# ic-mhm-encoder-simple.net
KiCad netlist of a schematic drawn in EAGLE
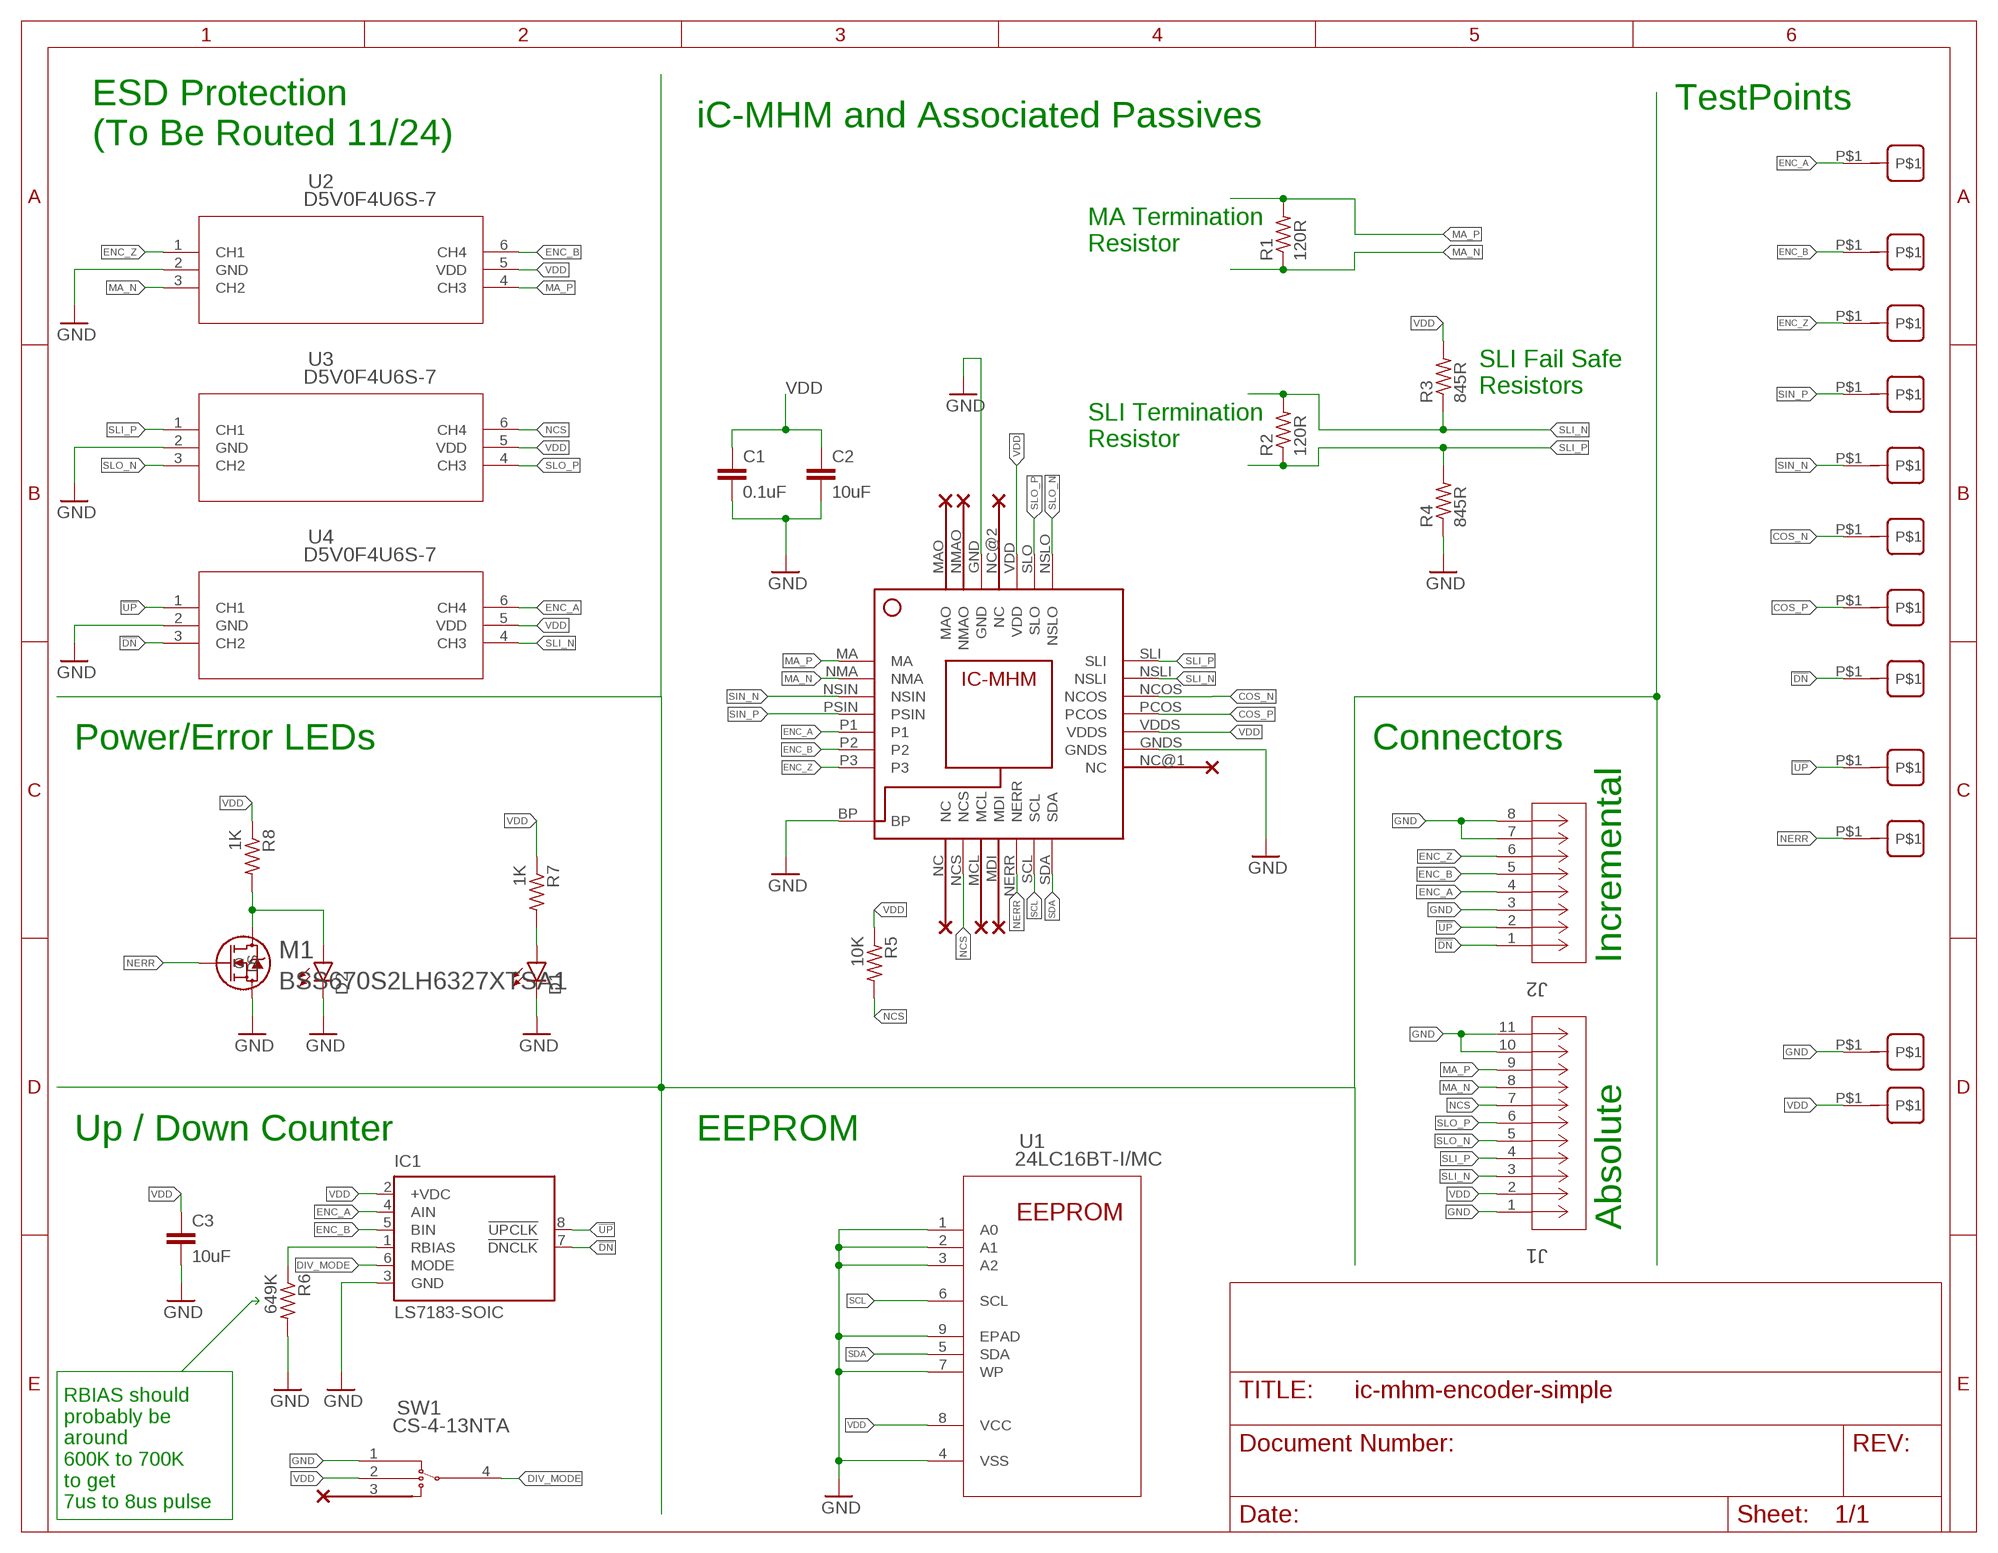
[diagram p0: schematic, sheet 1]

(export (version "E")
  (design (tool "Eeschema 10.0.6"))
  (components
    (comp (ref "C1")
      (value "0.1uF")
      (footprint "eagle-import:C0603")
      (libsource (lib "eagle-import") (part "C-EUC0603"))
    )
    (comp (ref "C2")
      (value "10uF")
      (footprint "eagle-import:C0805")
      (libsource (lib "eagle-import") (part "C-EUC0805"))
    )
    (comp (ref "C3")
      (value "10uF")
      (footprint "eagle-import:C0805")
      (libsource (lib "eagle-import") (part "C-EUC0805"))
    )
    (comp (ref "D1")
      (value "LEDSML0603")
      (footprint "eagle-import:SML0603")
      (libsource (lib "eagle-import") (part "LEDSML0603"))
    )
    (comp (ref "D2")
      (value "LEDSML0603")
      (footprint "eagle-import:SML0603")
      (libsource (lib "eagle-import") (part "LEDSML0603"))
    )
    (comp (ref "IC1")
      (value "LS7183-SOIC")
      (footprint "eagle-import:SOIC08")
      (fields
        (field (name "DIGI-KEY_PART_NUMBER") "2808-LS7183N-S-ND")
        (field (name "MF") "LSI")
        (field (name "MP") "LS7183")
      )
      (libsource (lib "eagle-import") (part "LS7183-SOIC"))
    )
    (comp (ref "J1")
      (value "2023960907")
      (footprint "eagle-import:CON_2023960907")
      (fields (field (name "COPYRIGHT") "Copyright (C) 2021 Ultra Librarian. All rights reserved."))
      (libsource (lib "eagle-import") (part "2023960907"))
    )
    (comp (ref "J2")
      (value "2023960607")
      (footprint "eagle-import:CON_2023960607")
      (fields (field (name "COPYRIGHT") "Copyright (C) 2021 Ultra Librarian. All rights reserved."))
      (libsource (lib "eagle-import") (part "2023960607"))
    )
    (comp (ref "M1")
      (value "BSS670S2LH6327XTSA1")
      (footprint "eagle-import:PG-SOT23-3-5_INF")
      (fields (field (name "COPYRIGHT") "Copyright (C) 2021 Ultra Librarian. All rights reserved."))
      (libsource (lib "eagle-import") (part "BSS670S2LH6327XTSA1"))
    )
    (comp (ref "R1")
      (value "120R")
      (footprint "eagle-import:R0603")
      (libsource (lib "eagle-import") (part "R-US_R0603"))
    )
    (comp (ref "R2")
      (value "120R")
      (footprint "eagle-import:R0603")
      (libsource (lib "eagle-import") (part "R-US_R0603"))
    )
    (comp (ref "R3")
      (value "845R")
      (footprint "eagle-import:R0603")
      (libsource (lib "eagle-import") (part "R-US_R0603"))
    )
    (comp (ref "R4")
      (value "845R")
      (footprint "eagle-import:R0603")
      (libsource (lib "eagle-import") (part "R-US_R0603"))
    )
    (comp (ref "R5")
      (value "10K")
      (footprint "eagle-import:R0603")
      (libsource (lib "eagle-import") (part "R-US_R0603"))
    )
    (comp (ref "R6")
      (value "649K")
      (footprint "eagle-import:R0603")
      (libsource (lib "eagle-import") (part "R-US_R0603"))
    )
    (comp (ref "R7")
      (value "1K")
      (footprint "eagle-import:R0603")
      (libsource (lib "eagle-import") (part "R-US_R0603"))
    )
    (comp (ref "R8")
      (value "1K")
      (footprint "eagle-import:R0603")
      (libsource (lib "eagle-import") (part "R-US_R0603"))
    )
    (comp (ref "SW1")
      (value "CS-4-13NTA")
      (footprint "eagle-import:CS-4-13NA_NDC")
      (fields (field (name "COPYRIGHT") "Copyright (C) 2021 Ultra Librarian. All rights reserved."))
      (libsource (lib "eagle-import") (part "CS-4-13NTA"))
    )
    (comp (ref "U$1")
      (value "IC-MHM")
      (footprint "eagle-import:IC-MHM")
      (libsource (lib "eagle-import") (part "IC-MHM"))
    )
    (comp (ref "U$2")
      (value "TESTPOINT_S1751-46")
      (footprint "eagle-import:TESTPOINT_S1751-46")
      (libsource (lib "eagle-import") (part "TESTPOINT_S1751-46"))
    )
    (comp (ref "U$3")
      (value "TESTPOINT_S1751-46")
      (footprint "eagle-import:TESTPOINT_S1751-46")
      (libsource (lib "eagle-import") (part "TESTPOINT_S1751-46"))
    )
    (comp (ref "U$4")
      (value "TESTPOINT_S1751-46")
      (footprint "eagle-import:TESTPOINT_S1751-46")
      (libsource (lib "eagle-import") (part "TESTPOINT_S1751-46"))
    )
    (comp (ref "U$5")
      (value "TESTPOINT_S1751-46")
      (footprint "eagle-import:TESTPOINT_S1751-46")
      (libsource (lib "eagle-import") (part "TESTPOINT_S1751-46"))
    )
    (comp (ref "U$6")
      (value "TESTPOINT_S1751-46")
      (footprint "eagle-import:TESTPOINT_S1751-46")
      (libsource (lib "eagle-import") (part "TESTPOINT_S1751-46"))
    )
    (comp (ref "U$7")
      (value "TESTPOINT_S1751-46")
      (footprint "eagle-import:TESTPOINT_S1751-46")
      (libsource (lib "eagle-import") (part "TESTPOINT_S1751-46"))
    )
    (comp (ref "U$8")
      (value "TESTPOINT_S1751-46")
      (footprint "eagle-import:TESTPOINT_S1751-46")
      (libsource (lib "eagle-import") (part "TESTPOINT_S1751-46"))
    )
    (comp (ref "U$9")
      (value "TESTPOINT_S1751-46")
      (footprint "eagle-import:TESTPOINT_S1751-46")
      (libsource (lib "eagle-import") (part "TESTPOINT_S1751-46"))
    )
    (comp (ref "U$10")
      (value "TESTPOINT_S1751-46")
      (footprint "eagle-import:TESTPOINT_S1751-46")
      (libsource (lib "eagle-import") (part "TESTPOINT_S1751-46"))
    )
    (comp (ref "U$11")
      (value "TESTPOINT_S1751-46")
      (footprint "eagle-import:TESTPOINT_S1751-46")
      (libsource (lib "eagle-import") (part "TESTPOINT_S1751-46"))
    )
    (comp (ref "U$15")
      (value "TESTPOINT_S1751-46")
      (footprint "eagle-import:TESTPOINT_S1751-46")
      (libsource (lib "eagle-import") (part "TESTPOINT_S1751-46"))
    )
    (comp (ref "U$16")
      (value "TESTPOINT_S1751-46")
      (footprint "eagle-import:TESTPOINT_S1751-46")
      (libsource (lib "eagle-import") (part "TESTPOINT_S1751-46"))
    )
    (comp (ref "U1")
      (value "24LC16BT-I/MC")
      (footprint "eagle-import:DFN8_2X3MC_MCH")
      (fields (field (name "COPYRIGHT") "Copyright (C) 2021 Ultra Librarian. All rights reserved."))
      (libsource (lib "eagle-import") (part "24LC16BT-I/MC"))
    )
    (comp (ref "U2")
      (value "D5V0F4U6S-7")
      (footprint "eagle-import:SOT-363_DIO")
      (fields (field (name "COPYRIGHT") "Copyright (C) 2021 Ultra Librarian. All rights reserved."))
      (libsource (lib "eagle-import") (part "D5V0F4U6S-7"))
    )
    (comp (ref "U3")
      (value "D5V0F4U6S-7")
      (footprint "eagle-import:SOT-363_DIO")
      (fields (field (name "COPYRIGHT") "Copyright (C) 2021 Ultra Librarian. All rights reserved."))
      (libsource (lib "eagle-import") (part "D5V0F4U6S-7"))
    )
    (comp (ref "U4")
      (value "D5V0F4U6S-7")
      (footprint "eagle-import:SOT-363_DIO")
      (fields (field (name "COPYRIGHT") "Copyright (C) 2021 Ultra Librarian. All rights reserved."))
      (libsource (lib "eagle-import") (part "D5V0F4U6S-7"))
    )
  )
  (nets
    (net (code "1") (name "/~{DN}") (class "Default")
      (node (ref "IC1") (pin "7") (pinfunction "~{DNCLK}_7") (pintype "input"))
      (node (ref "J2") (pin "1") (pinfunction "1_1") (pintype "passive"))
      (node (ref "U$8") (pin "P$1") (pinfunction "P$1_P$1") (pintype "bidirectional"))
      (node (ref "U4") (pin "3") (pinfunction "CH2_3") (pintype "passive"))
    )
    (net (code "2") (name "/~{UP}") (class "Default")
      (node (ref "IC1") (pin "8") (pinfunction "~{UPCLK}_8") (pintype "input"))
      (node (ref "J2") (pin "2") (pinfunction "2_2") (pintype "passive"))
      (node (ref "U$9") (pin "P$1") (pinfunction "P$1_P$1") (pintype "bidirectional"))
      (node (ref "U4") (pin "1") (pinfunction "CH1_1") (pintype "passive"))
    )
    (net (code "3") (name "COS_N") (class "Default")
      (node (ref "U$1") (pin "NCOS") (pinfunction "NCOS_NCOS") (pintype "bidirectional"))
      (node (ref "U$7") (pin "P$1") (pinfunction "P$1_P$1") (pintype "bidirectional"))
    )
    (net (code "4") (name "COS_P") (class "Default")
      (node (ref "U$1") (pin "PCOS") (pinfunction "PCOS_PCOS") (pintype "bidirectional"))
      (node (ref "U$11") (pin "P$1") (pinfunction "P$1_P$1") (pintype "bidirectional"))
    )
    (net (code "5") (name "DIV_MODE") (class "Default")
      (node (ref "IC1") (pin "6") (pinfunction "MODE_6") (pintype "input"))
      (node (ref "SW1") (pin "4") (pinfunction "4_4") (pintype "passive"))
    )
    (net (code "6") (name "ENC_A") (class "Default")
      (node (ref "IC1") (pin "4") (pinfunction "AIN_4") (pintype "input"))
      (node (ref "J2") (pin "4") (pinfunction "4_4") (pintype "passive"))
      (node (ref "U$1") (pin "P1") (pinfunction "P1_P1") (pintype "bidirectional"))
      (node (ref "U$2") (pin "P$1") (pinfunction "P$1_P$1") (pintype "bidirectional"))
      (node (ref "U4") (pin "6") (pinfunction "CH4_6") (pintype "passive"))
    )
    (net (code "7") (name "ENC_B") (class "Default")
      (node (ref "IC1") (pin "5") (pinfunction "BIN_5") (pintype "input"))
      (node (ref "J2") (pin "5") (pinfunction "5_5") (pintype "passive"))
      (node (ref "U$1") (pin "P2") (pinfunction "P2_P2") (pintype "bidirectional"))
      (node (ref "U$3") (pin "P$1") (pinfunction "P$1_P$1") (pintype "bidirectional"))
      (node (ref "U2") (pin "6") (pinfunction "CH4_6") (pintype "passive"))
    )
    (net (code "8") (name "ENC_Z") (class "Default")
      (node (ref "J2") (pin "6") (pinfunction "6_6") (pintype "passive"))
      (node (ref "U$1") (pin "P3") (pinfunction "P3_P3") (pintype "bidirectional"))
      (node (ref "U$4") (pin "P$1") (pinfunction "P$1_P$1") (pintype "bidirectional"))
      (node (ref "U2") (pin "1") (pinfunction "CH1_1") (pintype "passive"))
    )
    (net (code "9") (name "GND") (class "Default")
      (node (ref "C1") (pin "2") (pinfunction "2_2") (pintype "passive"))
      (node (ref "C2") (pin "2") (pinfunction "2_2") (pintype "passive"))
      (node (ref "C3") (pin "2") (pinfunction "2_2") (pintype "passive"))
      (node (ref "D1") (pin "C") (pinfunction "C_C") (pintype "passive"))
      (node (ref "D2") (pin "C") (pinfunction "C_C") (pintype "passive"))
      (node (ref "IC1") (pin "3") (pinfunction "GND_3") (pintype "power_in"))
      (node (ref "J1") (pin "1") (pinfunction "1_1") (pintype "passive"))
      (node (ref "J1") (pin "10") (pinfunction "10_10") (pintype "passive"))
      (node (ref "J1") (pin "11") (pinfunction "11_11") (pintype "passive"))
      (node (ref "J2") (pin "3") (pinfunction "3_3") (pintype "passive"))
      (node (ref "J2") (pin "7") (pinfunction "7_7") (pintype "passive"))
      (node (ref "J2") (pin "8") (pinfunction "8_8") (pintype "passive"))
      (node (ref "M1") (pin "2") (pinfunction "S_2") (pintype "passive"))
      (node (ref "R4") (pin "1") (pinfunction "1_1") (pintype "passive"))
      (node (ref "R6") (pin "2") (pinfunction "2_2") (pintype "passive"))
      (node (ref "SW1") (pin "1") (pinfunction "1_1") (pintype "passive"))
      (node (ref "U$1") (pin "BP") (pinfunction "BP_BP") (pintype "bidirectional"))
      (node (ref "U$1") (pin "GND") (pinfunction "GND_GND") (pintype "bidirectional"))
      (node (ref "U$1") (pin "GNDS") (pinfunction "GNDS_GNDS") (pintype "bidirectional"))
      (node (ref "U$15") (pin "P$1") (pinfunction "P$1_P$1") (pintype "bidirectional"))
      (node (ref "U1") (pin "1") (pinfunction "A0_1") (pintype "input"))
      (node (ref "U1") (pin "2") (pinfunction "A1_2") (pintype "input"))
      (node (ref "U1") (pin "3") (pinfunction "A2_3") (pintype "input"))
      (node (ref "U1") (pin "4") (pinfunction "VSS_4") (pintype "power_in"))
      (node (ref "U1") (pin "7") (pinfunction "WP_7") (pintype "passive"))
      (node (ref "U1") (pin "9") (pinfunction "EPAD_9") (pintype "passive"))
      (node (ref "U2") (pin "2") (pinfunction "GND_2") (pintype "power_in"))
      (node (ref "U3") (pin "2") (pinfunction "GND_2") (pintype "power_in"))
      (node (ref "U4") (pin "2") (pinfunction "GND_2") (pintype "power_in"))
    )
    (net (code "10") (name "MA_N") (class "Default")
      (node (ref "J1") (pin "8") (pinfunction "8_8") (pintype "passive"))
      (node (ref "R1") (pin "1") (pinfunction "1_1") (pintype "passive"))
      (node (ref "U$1") (pin "NMA") (pinfunction "NMA_NMA") (pintype "bidirectional"))
      (node (ref "U2") (pin "3") (pinfunction "CH2_3") (pintype "passive"))
    )
    (net (code "11") (name "MA_P") (class "Default")
      (node (ref "J1") (pin "9") (pinfunction "9_9") (pintype "passive"))
      (node (ref "R1") (pin "2") (pinfunction "2_2") (pintype "passive"))
      (node (ref "U$1") (pin "MA") (pinfunction "MA_MA") (pintype "bidirectional"))
      (node (ref "U2") (pin "4") (pinfunction "CH3_4") (pintype "passive"))
    )
    (net (code "12") (name "NCS") (class "Default")
      (node (ref "J1") (pin "7") (pinfunction "7_7") (pintype "passive"))
      (node (ref "R5") (pin "2") (pinfunction "2_2") (pintype "passive"))
      (node (ref "U$1") (pin "NCS") (pinfunction "NCS_NCS") (pintype "bidirectional"))
      (node (ref "U3") (pin "6") (pinfunction "CH4_6") (pintype "passive"))
    )
    (net (code "13") (name "NERR") (class "Default")
      (node (ref "M1") (pin "1") (pinfunction "G_1") (pintype "passive"))
      (node (ref "U$1") (pin "NERR") (pinfunction "NERR_NERR") (pintype "bidirectional"))
      (node (ref "U$10") (pin "P$1") (pinfunction "P$1_P$1") (pintype "bidirectional"))
    )
    (net (code "14") (name "Net-(D1-PadA)") (class "Default")
      (node (ref "D1") (pin "A") (pinfunction "A_A") (pintype "passive"))
      (node (ref "R7") (pin "2") (pinfunction "2_2") (pintype "passive"))
    )
    (net (code "15") (name "Net-(IC1-RBIAS)") (class "Default")
      (node (ref "IC1") (pin "1") (pinfunction "RBIAS_1") (pintype "input"))
      (node (ref "R6") (pin "1") (pinfunction "1_1") (pintype "passive"))
    )
    (net (code "16") (name "Net-(M1-D)") (class "Default")
      (node (ref "D2") (pin "A") (pinfunction "A_A") (pintype "passive"))
      (node (ref "M1") (pin "3") (pinfunction "D_3") (pintype "passive"))
      (node (ref "R8") (pin "2") (pinfunction "2_2") (pintype "passive"))
    )
    (net (code "17") (name "SCL") (class "Default")
      (node (ref "U$1") (pin "SCL") (pinfunction "SCL_SCL") (pintype "bidirectional"))
      (node (ref "U1") (pin "6") (pinfunction "SCL_6") (pintype "input"))
    )
    (net (code "18") (name "SDA") (class "Default")
      (node (ref "U$1") (pin "SDA") (pinfunction "SDA_SDA") (pintype "bidirectional"))
      (node (ref "U1") (pin "5") (pinfunction "SDA_5") (pintype "bidirectional"))
    )
    (net (code "19") (name "SIN_N") (class "Default")
      (node (ref "U$1") (pin "NSIN") (pinfunction "NSIN_NSIN") (pintype "bidirectional"))
      (node (ref "U$6") (pin "P$1") (pinfunction "P$1_P$1") (pintype "bidirectional"))
    )
    (net (code "20") (name "SIN_P") (class "Default")
      (node (ref "U$1") (pin "PSIN") (pinfunction "PSIN_PSIN") (pintype "bidirectional"))
      (node (ref "U$5") (pin "P$1") (pinfunction "P$1_P$1") (pintype "bidirectional"))
    )
    (net (code "21") (name "SLI_N") (class "Default")
      (node (ref "J1") (pin "3") (pinfunction "3_3") (pintype "passive"))
      (node (ref "R2") (pin "2") (pinfunction "2_2") (pintype "passive"))
      (node (ref "R3") (pin "1") (pinfunction "1_1") (pintype "passive"))
      (node (ref "U$1") (pin "NSLI") (pinfunction "NSLI_NSLI") (pintype "bidirectional"))
      (node (ref "U4") (pin "4") (pinfunction "CH3_4") (pintype "passive"))
    )
    (net (code "22") (name "SLI_P") (class "Default")
      (node (ref "J1") (pin "4") (pinfunction "4_4") (pintype "passive"))
      (node (ref "R2") (pin "1") (pinfunction "1_1") (pintype "passive"))
      (node (ref "R4") (pin "2") (pinfunction "2_2") (pintype "passive"))
      (node (ref "U$1") (pin "SLI") (pinfunction "SLI_SLI") (pintype "bidirectional"))
      (node (ref "U3") (pin "1") (pinfunction "CH1_1") (pintype "passive"))
    )
    (net (code "23") (name "SLO_N") (class "Default")
      (node (ref "J1") (pin "5") (pinfunction "5_5") (pintype "passive"))
      (node (ref "U$1") (pin "NSLO") (pinfunction "NSLO_NSLO") (pintype "bidirectional"))
      (node (ref "U3") (pin "3") (pinfunction "CH2_3") (pintype "passive"))
    )
    (net (code "24") (name "SLO_P") (class "Default")
      (node (ref "J1") (pin "6") (pinfunction "6_6") (pintype "passive"))
      (node (ref "U$1") (pin "SLO") (pinfunction "SLO_SLO") (pintype "bidirectional"))
      (node (ref "U3") (pin "4") (pinfunction "CH3_4") (pintype "passive"))
    )
    (net (code "25") (name "VDD") (class "Default")
      (node (ref "C1") (pin "1") (pinfunction "1_1") (pintype "passive"))
      (node (ref "C2") (pin "1") (pinfunction "1_1") (pintype "passive"))
      (node (ref "C3") (pin "1") (pinfunction "1_1") (pintype "passive"))
      (node (ref "IC1") (pin "2") (pinfunction "+VDC_2") (pintype "input"))
      (node (ref "J1") (pin "2") (pinfunction "2_2") (pintype "passive"))
      (node (ref "R3") (pin "2") (pinfunction "2_2") (pintype "passive"))
      (node (ref "R5") (pin "1") (pinfunction "1_1") (pintype "passive"))
      (node (ref "R7") (pin "1") (pinfunction "1_1") (pintype "passive"))
      (node (ref "R8") (pin "1") (pinfunction "1_1") (pintype "passive"))
      (node (ref "SW1") (pin "2") (pinfunction "2_2") (pintype "passive"))
      (node (ref "U$1") (pin "VDD") (pinfunction "VDD_VDD") (pintype "bidirectional"))
      (node (ref "U$1") (pin "VDDS") (pinfunction "VDDS_VDDS") (pintype "bidirectional"))
      (node (ref "U$16") (pin "P$1") (pinfunction "P$1_P$1") (pintype "bidirectional"))
      (node (ref "U1") (pin "8") (pinfunction "VCC_8") (pintype "power_in"))
      (node (ref "U2") (pin "5") (pinfunction "VDD_5") (pintype "power_in"))
      (node (ref "U3") (pin "5") (pinfunction "VDD_5") (pintype "power_in"))
      (node (ref "U4") (pin "5") (pinfunction "VDD_5") (pintype "power_in"))
    )
    (net (code "26") (name "unconnected-(SW1-Pad3)") (class "Default")
      (node (ref "SW1") (pin "3") (pinfunction "3_3") (pintype "passive"))
    )
    (net (code "27") (name "unconnected-(U$1-NC-PadNC@1)") (class "Default")
      (node (ref "U$1") (pin "NC@1") (pinfunction "NC_NC@1") (pintype "bidirectional"))
    )
    (net (code "28") (name "unconnected-(U$1-NC-PadNC@2)") (class "Default")
      (node (ref "U$1") (pin "NC@2") (pinfunction "NC_NC@2") (pintype "bidirectional"))
    )
    (net (code "29") (name "unconnected-(U$1-PadMAO)") (class "Default")
      (node (ref "U$1") (pin "MAO") (pinfunction "MAO_MAO") (pintype "bidirectional"))
    )
    (net (code "30") (name "unconnected-(U$1-PadMCL)") (class "Default")
      (node (ref "U$1") (pin "MCL") (pinfunction "MCL_MCL") (pintype "bidirectional"))
    )
    (net (code "31") (name "unconnected-(U$1-PadMDI)") (class "Default")
      (node (ref "U$1") (pin "MDI") (pinfunction "MDI_MDI") (pintype "bidirectional"))
    )
    (net (code "32") (name "unconnected-(U$1-PadNC)") (class "Default")
      (node (ref "U$1") (pin "NC") (pinfunction "NC_NC") (pintype "bidirectional"))
    )
    (net (code "33") (name "unconnected-(U$1-PadNMAO)") (class "Default")
      (node (ref "U$1") (pin "NMAO") (pinfunction "NMAO_NMAO") (pintype "bidirectional"))
    )
  )
)
